# IO_board-ha-v3-rev1.net
KiCad netlist of a schematic drawn in EAGLE
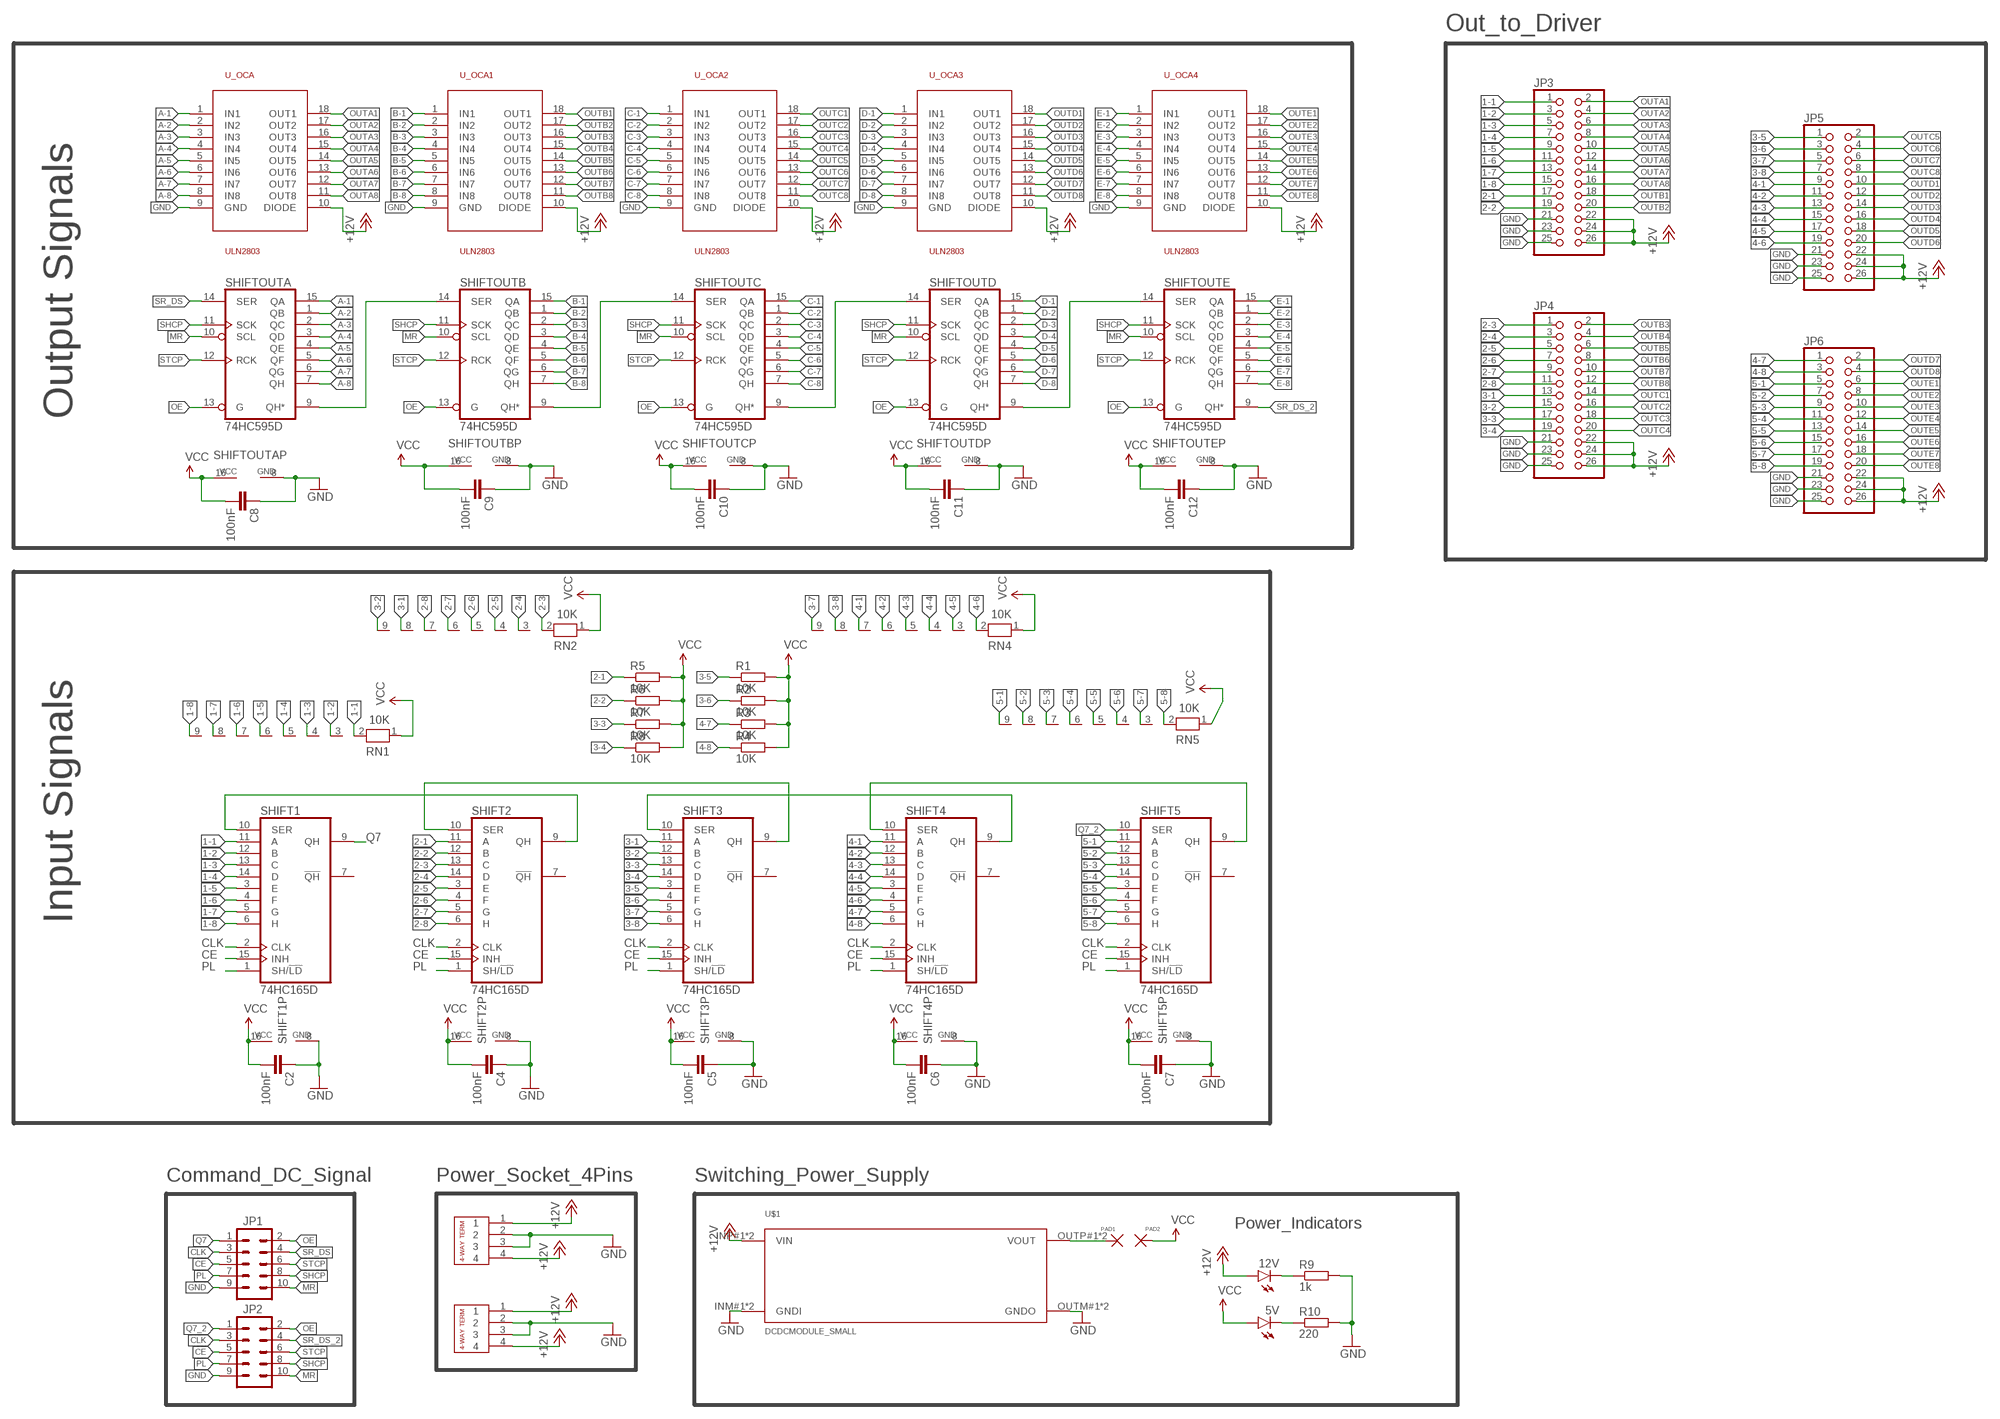
[diagram p0: schematic, sheet 1]

(export (version "E")
  (design (tool "Eeschema 10.0.6"))
  (components
    (comp (ref "5V")
      (value "LED3MM")
      (footprint "eagle-import:LED3MM")
      (libsource (lib "eagle-import") (part "LED3MM"))
    )
    (comp (ref "12V")
      (value "LED3MM")
      (footprint "eagle-import:LED3MM")
      (libsource (lib "eagle-import") (part "LED3MM"))
    )
    (comp (ref "C2")
      (value "100nF")
      (footprint "eagle-import:C0603K")
      (libsource (lib "eagle-import") (part "C-EUC0603K"))
    )
    (comp (ref "C4")
      (value "100nF")
      (footprint "eagle-import:C0603K")
      (libsource (lib "eagle-import") (part "C-EUC0603K"))
    )
    (comp (ref "C5")
      (value "100nF")
      (footprint "eagle-import:C0603K")
      (libsource (lib "eagle-import") (part "C-EUC0603K"))
    )
    (comp (ref "C6")
      (value "100nF")
      (footprint "eagle-import:C0603K")
      (libsource (lib "eagle-import") (part "C-EUC0603K"))
    )
    (comp (ref "C7")
      (value "100nF")
      (footprint "eagle-import:C0603K")
      (libsource (lib "eagle-import") (part "C-EUC0603K"))
    )
    (comp (ref "C8")
      (value "100nF")
      (footprint "eagle-import:C0603K")
      (libsource (lib "eagle-import") (part "C-EUC0603K"))
    )
    (comp (ref "C9")
      (value "100nF")
      (footprint "eagle-import:C0603K")
      (libsource (lib "eagle-import") (part "C-EUC0603K"))
    )
    (comp (ref "C10")
      (value "100nF")
      (footprint "eagle-import:C0603K")
      (libsource (lib "eagle-import") (part "C-EUC0603K"))
    )
    (comp (ref "C11")
      (value "100nF")
      (footprint "eagle-import:C0603K")
      (libsource (lib "eagle-import") (part "C-EUC0603K"))
    )
    (comp (ref "C12")
      (value "100nF")
      (footprint "eagle-import:C0603K")
      (libsource (lib "eagle-import") (part "C-EUC0603K"))
    )
    (comp (ref "J1")
      (value "4-PIN-CON-1759017")
      (footprint "eagle-import:4-PIN-CON-1759017")
      (libsource (lib "eagle-import") (part "4-PIN-CON-1759017"))
    )
    (comp (ref "J2")
      (value "4-PIN-CON-1759017")
      (footprint "eagle-import:4-PIN-CON-1759017")
      (libsource (lib "eagle-import") (part "4-PIN-CON-1759017"))
    )
    (comp (ref "JP1")
      (value "M05X2SHD")
      (footprint "eagle-import:2X5-SHROUDED")
      (libsource (lib "eagle-import") (part "M05X2SHD"))
    )
    (comp (ref "JP2")
      (value "M05X2SHD")
      (footprint "eagle-import:2X5-SHROUDED")
      (libsource (lib "eagle-import") (part "M05X2SHD"))
    )
    (comp (ref "JP3")
      (value "PINHD-2X13")
      (footprint "eagle-import:2X13")
      (libsource (lib "eagle-import") (part "PINHD-2X13"))
    )
    (comp (ref "JP4")
      (value "PINHD-2X13")
      (footprint "eagle-import:2X13")
      (libsource (lib "eagle-import") (part "PINHD-2X13"))
    )
    (comp (ref "JP5")
      (value "PINHD-2X13")
      (footprint "eagle-import:2X13")
      (libsource (lib "eagle-import") (part "PINHD-2X13"))
    )
    (comp (ref "JP6")
      (value "PINHD-2X13")
      (footprint "eagle-import:2X13")
      (libsource (lib "eagle-import") (part "PINHD-2X13"))
    )
    (comp (ref "R1")
      (value "10K")
      (footprint "eagle-import:R0603")
      (libsource (lib "eagle-import") (part "resistor_R-EU_R0603"))
    )
    (comp (ref "R2")
      (value "10K")
      (footprint "eagle-import:R0603")
      (libsource (lib "eagle-import") (part "resistor_R-EU_R0603"))
    )
    (comp (ref "R3")
      (value "10K")
      (footprint "eagle-import:R0603")
      (libsource (lib "eagle-import") (part "resistor_R-EU_R0603"))
    )
    (comp (ref "R4")
      (value "10K")
      (footprint "eagle-import:R0603")
      (libsource (lib "eagle-import") (part "resistor_R-EU_R0603"))
    )
    (comp (ref "R5")
      (value "10K")
      (footprint "eagle-import:R0603")
      (libsource (lib "eagle-import") (part "resistor_R-EU_R0603"))
    )
    (comp (ref "R6")
      (value "10K")
      (footprint "eagle-import:R0603")
      (libsource (lib "eagle-import") (part "resistor_R-EU_R0603"))
    )
    (comp (ref "R7")
      (value "10K")
      (footprint "eagle-import:R0603")
      (libsource (lib "eagle-import") (part "resistor_R-EU_R0603"))
    )
    (comp (ref "R8")
      (value "10K")
      (footprint "eagle-import:R0603")
      (libsource (lib "eagle-import") (part "resistor_R-EU_R0603"))
    )
    (comp (ref "R9")
      (value "1k")
      (footprint "eagle-import:R0805")
      (libsource (lib "eagle-import") (part "R-EU_R0805"))
    )
    (comp (ref "R10")
      (value "220")
      (footprint "eagle-import:R0805")
      (libsource (lib "eagle-import") (part "R-EU_R0805"))
    )
    (comp (ref "RN1")
      (value "10K")
      (footprint "eagle-import:RN-9")
      (libsource (lib "eagle-import") (part "RN08"))
    )
    (comp (ref "RN2")
      (value "10K")
      (footprint "eagle-import:RN-9")
      (libsource (lib "eagle-import") (part "RN08"))
    )
    (comp (ref "RN4")
      (value "10K")
      (footprint "eagle-import:RN-9")
      (libsource (lib "eagle-import") (part "RN08"))
    )
    (comp (ref "RN5")
      (value "10K")
      (footprint "eagle-import:RN-9")
      (libsource (lib "eagle-import") (part "RN08"))
    )
    (comp (ref "SHIFT1")
      (value "74HC165D")
      (footprint "eagle-import:SO16")
      (libsource (lib "eagle-import") (part "74165DHC"))
    )
    (comp (ref "SHIFT2")
      (value "74HC165D")
      (footprint "eagle-import:SO16")
      (libsource (lib "eagle-import") (part "74165DHC"))
    )
    (comp (ref "SHIFT3")
      (value "74HC165D")
      (footprint "eagle-import:SO16")
      (libsource (lib "eagle-import") (part "74165DHC"))
    )
    (comp (ref "SHIFT4")
      (value "74HC165D")
      (footprint "eagle-import:SO16")
      (libsource (lib "eagle-import") (part "74165DHC"))
    )
    (comp (ref "SHIFT5")
      (value "74HC165D")
      (footprint "eagle-import:SO16")
      (libsource (lib "eagle-import") (part "74165DHC"))
    )
    (comp (ref "SHIFTOUTA")
      (value "74HC595D")
      (footprint "eagle-import:SO16")
      (libsource (lib "eagle-import") (part "74595DHC"))
    )
    (comp (ref "SHIFTOUTB")
      (value "74HC595D")
      (footprint "eagle-import:SO16")
      (libsource (lib "eagle-import") (part "74595DHC"))
    )
    (comp (ref "SHIFTOUTC")
      (value "74HC595D")
      (footprint "eagle-import:SO16")
      (libsource (lib "eagle-import") (part "74595DHC"))
    )
    (comp (ref "SHIFTOUTD")
      (value "74HC595D")
      (footprint "eagle-import:SO16")
      (libsource (lib "eagle-import") (part "74595DHC"))
    )
    (comp (ref "SHIFTOUTE")
      (value "74HC595D")
      (footprint "eagle-import:SO16")
      (libsource (lib "eagle-import") (part "74595DHC"))
    )
    (comp (ref "U$1")
      (value "DCDCMODULE_SMALL")
      (footprint "eagle-import:DCDCMODULE-SMALL")
      (libsource (lib "eagle-import") (part "DCDCMODULE_SMALL"))
    )
    (comp (ref "U$2")
      (value "DOUBLE_SMALL_PAD")
      (footprint "eagle-import:DOUBLE_SMALL_PAD")
      (libsource (lib "eagle-import") (part "DOUBLE_SMALL_PAD"))
    )
    (comp (ref "U_OCA")
      (value "ULN2803")
      (footprint "eagle-import:SO18L")
      (libsource (lib "eagle-import") (part "ULN2803"))
    )
    (comp (ref "U_OCA1")
      (value "ULN2803")
      (footprint "eagle-import:SO18L")
      (libsource (lib "eagle-import") (part "ULN2803"))
    )
    (comp (ref "U_OCA2")
      (value "ULN2803")
      (footprint "eagle-import:SO18L")
      (libsource (lib "eagle-import") (part "ULN2803"))
    )
    (comp (ref "U_OCA3")
      (value "ULN2803")
      (footprint "eagle-import:SO18L")
      (libsource (lib "eagle-import") (part "ULN2803"))
    )
    (comp (ref "U_OCA4")
      (value "ULN2803")
      (footprint "eagle-import:SO18L")
      (libsource (lib "eagle-import") (part "ULN2803"))
    )
  )
  (nets
    (net (code "1") (name "+12V") (class "Default")
      (node (ref "12V") (pin "A") (pinfunction "A_A") (pintype "passive"))
      (node (ref "J1") (pin "1") (pinfunction "1_1") (pintype "bidirectional"))
      (node (ref "J1") (pin "4") (pinfunction "4_4") (pintype "bidirectional"))
      (node (ref "J2") (pin "1") (pinfunction "1_1") (pintype "bidirectional"))
      (node (ref "J2") (pin "4") (pinfunction "4_4") (pintype "bidirectional"))
      (node (ref "JP3") (pin "22") (pinfunction "22_22") (pintype "passive"))
      (node (ref "JP3") (pin "24") (pinfunction "24_24") (pintype "passive"))
      (node (ref "JP3") (pin "26") (pinfunction "26_26") (pintype "passive"))
      (node (ref "JP4") (pin "22") (pinfunction "22_22") (pintype "passive"))
      (node (ref "JP4") (pin "24") (pinfunction "24_24") (pintype "passive"))
      (node (ref "JP4") (pin "26") (pinfunction "26_26") (pintype "passive"))
      (node (ref "JP5") (pin "22") (pinfunction "22_22") (pintype "passive"))
      (node (ref "JP5") (pin "24") (pinfunction "24_24") (pintype "passive"))
      (node (ref "JP5") (pin "26") (pinfunction "26_26") (pintype "passive"))
      (node (ref "JP6") (pin "22") (pinfunction "22_22") (pintype "passive"))
      (node (ref "JP6") (pin "24") (pinfunction "24_24") (pintype "passive"))
      (node (ref "JP6") (pin "26") (pinfunction "26_26") (pintype "passive"))
      (node (ref "U$1") (pin "INP#1") (pinfunction "VIN_INP#1") (pintype "bidirectional"))
      (node (ref "U$1") (pin "INP#2") (pinfunction "VIN_INP#2") (pintype "bidirectional"))
      (node (ref "U_OCA") (pin "10") (pinfunction "DIODE_10") (pintype "power_in"))
      (node (ref "U_OCA1") (pin "10") (pinfunction "DIODE_10") (pintype "power_in"))
      (node (ref "U_OCA2") (pin "10") (pinfunction "DIODE_10") (pintype "power_in"))
      (node (ref "U_OCA3") (pin "10") (pinfunction "DIODE_10") (pintype "power_in"))
      (node (ref "U_OCA4") (pin "10") (pinfunction "DIODE_10") (pintype "power_in"))
    )
    (net (code "2") (name "1-1") (class "Default")
      (node (ref "JP3") (pin "1") (pinfunction "1_1") (pintype "passive"))
      (node (ref "RN1") (pin "2") (pinfunction "2_2") (pintype "passive"))
      (node (ref "SHIFT1") (pin "11") (pinfunction "A_11") (pintype "input"))
    )
    (net (code "3") (name "1-2") (class "Default")
      (node (ref "JP3") (pin "3") (pinfunction "3_3") (pintype "passive"))
      (node (ref "RN1") (pin "3") (pinfunction "3_3") (pintype "passive"))
      (node (ref "SHIFT1") (pin "12") (pinfunction "B_12") (pintype "input"))
    )
    (net (code "4") (name "1-3") (class "Default")
      (node (ref "JP3") (pin "5") (pinfunction "5_5") (pintype "passive"))
      (node (ref "RN1") (pin "4") (pinfunction "4_4") (pintype "passive"))
      (node (ref "SHIFT1") (pin "13") (pinfunction "C_13") (pintype "input"))
    )
    (net (code "5") (name "1-4") (class "Default")
      (node (ref "JP3") (pin "7") (pinfunction "7_7") (pintype "passive"))
      (node (ref "RN1") (pin "5") (pinfunction "5_5") (pintype "passive"))
      (node (ref "SHIFT1") (pin "14") (pinfunction "D_14") (pintype "input"))
    )
    (net (code "6") (name "1-5") (class "Default")
      (node (ref "JP3") (pin "9") (pinfunction "9_9") (pintype "passive"))
      (node (ref "RN1") (pin "6") (pinfunction "6_6") (pintype "passive"))
      (node (ref "SHIFT1") (pin "3") (pinfunction "E_3") (pintype "input"))
    )
    (net (code "7") (name "1-6") (class "Default")
      (node (ref "JP3") (pin "11") (pinfunction "11_11") (pintype "passive"))
      (node (ref "RN1") (pin "7") (pinfunction "7_7") (pintype "passive"))
      (node (ref "SHIFT1") (pin "4") (pinfunction "F_4") (pintype "input"))
    )
    (net (code "8") (name "1-7") (class "Default")
      (node (ref "JP3") (pin "13") (pinfunction "13_13") (pintype "passive"))
      (node (ref "RN1") (pin "8") (pinfunction "8_8") (pintype "passive"))
      (node (ref "SHIFT1") (pin "5") (pinfunction "G_5") (pintype "input"))
    )
    (net (code "9") (name "1-8") (class "Default")
      (node (ref "JP3") (pin "15") (pinfunction "15_15") (pintype "passive"))
      (node (ref "RN1") (pin "9") (pinfunction "9_9") (pintype "passive"))
      (node (ref "SHIFT1") (pin "6") (pinfunction "H_6") (pintype "input"))
    )
    (net (code "10") (name "2-1") (class "Default")
      (node (ref "JP3") (pin "17") (pinfunction "17_17") (pintype "passive"))
      (node (ref "R5") (pin "1") (pinfunction "1_1") (pintype "passive"))
      (node (ref "SHIFT2") (pin "11") (pinfunction "A_11") (pintype "input"))
    )
    (net (code "11") (name "2-2") (class "Default")
      (node (ref "JP3") (pin "19") (pinfunction "19_19") (pintype "passive"))
      (node (ref "R6") (pin "1") (pinfunction "1_1") (pintype "passive"))
      (node (ref "SHIFT2") (pin "12") (pinfunction "B_12") (pintype "input"))
    )
    (net (code "12") (name "2-3") (class "Default")
      (node (ref "JP4") (pin "1") (pinfunction "1_1") (pintype "passive"))
      (node (ref "RN2") (pin "2") (pinfunction "2_2") (pintype "passive"))
      (node (ref "SHIFT2") (pin "13") (pinfunction "C_13") (pintype "input"))
    )
    (net (code "13") (name "2-4") (class "Default")
      (node (ref "JP4") (pin "3") (pinfunction "3_3") (pintype "passive"))
      (node (ref "RN2") (pin "3") (pinfunction "3_3") (pintype "passive"))
      (node (ref "SHIFT2") (pin "14") (pinfunction "D_14") (pintype "input"))
    )
    (net (code "14") (name "2-5") (class "Default")
      (node (ref "JP4") (pin "5") (pinfunction "5_5") (pintype "passive"))
      (node (ref "RN2") (pin "4") (pinfunction "4_4") (pintype "passive"))
      (node (ref "SHIFT2") (pin "3") (pinfunction "E_3") (pintype "input"))
    )
    (net (code "15") (name "2-6") (class "Default")
      (node (ref "JP4") (pin "7") (pinfunction "7_7") (pintype "passive"))
      (node (ref "RN2") (pin "5") (pinfunction "5_5") (pintype "passive"))
      (node (ref "SHIFT2") (pin "4") (pinfunction "F_4") (pintype "input"))
    )
    (net (code "16") (name "2-7") (class "Default")
      (node (ref "JP4") (pin "9") (pinfunction "9_9") (pintype "passive"))
      (node (ref "RN2") (pin "6") (pinfunction "6_6") (pintype "passive"))
      (node (ref "SHIFT2") (pin "5") (pinfunction "G_5") (pintype "input"))
    )
    (net (code "17") (name "2-8") (class "Default")
      (node (ref "JP4") (pin "11") (pinfunction "11_11") (pintype "passive"))
      (node (ref "RN2") (pin "7") (pinfunction "7_7") (pintype "passive"))
      (node (ref "SHIFT2") (pin "6") (pinfunction "H_6") (pintype "input"))
    )
    (net (code "18") (name "3-1") (class "Default")
      (node (ref "JP4") (pin "13") (pinfunction "13_13") (pintype "passive"))
      (node (ref "RN2") (pin "8") (pinfunction "8_8") (pintype "passive"))
      (node (ref "SHIFT3") (pin "11") (pinfunction "A_11") (pintype "input"))
    )
    (net (code "19") (name "3-2") (class "Default")
      (node (ref "JP4") (pin "15") (pinfunction "15_15") (pintype "passive"))
      (node (ref "RN2") (pin "9") (pinfunction "9_9") (pintype "passive"))
      (node (ref "SHIFT3") (pin "12") (pinfunction "B_12") (pintype "input"))
    )
    (net (code "20") (name "3-3") (class "Default")
      (node (ref "JP4") (pin "17") (pinfunction "17_17") (pintype "passive"))
      (node (ref "R7") (pin "1") (pinfunction "1_1") (pintype "passive"))
      (node (ref "SHIFT3") (pin "13") (pinfunction "C_13") (pintype "input"))
    )
    (net (code "21") (name "3-4") (class "Default")
      (node (ref "JP4") (pin "19") (pinfunction "19_19") (pintype "passive"))
      (node (ref "R8") (pin "1") (pinfunction "1_1") (pintype "passive"))
      (node (ref "SHIFT3") (pin "14") (pinfunction "D_14") (pintype "input"))
    )
    (net (code "22") (name "3-5") (class "Default")
      (node (ref "JP5") (pin "1") (pinfunction "1_1") (pintype "passive"))
      (node (ref "R1") (pin "1") (pinfunction "1_1") (pintype "passive"))
      (node (ref "SHIFT3") (pin "3") (pinfunction "E_3") (pintype "input"))
    )
    (net (code "23") (name "3-6") (class "Default")
      (node (ref "JP5") (pin "3") (pinfunction "3_3") (pintype "passive"))
      (node (ref "R2") (pin "1") (pinfunction "1_1") (pintype "passive"))
      (node (ref "SHIFT3") (pin "4") (pinfunction "F_4") (pintype "input"))
    )
    (net (code "24") (name "3-7") (class "Default")
      (node (ref "JP5") (pin "5") (pinfunction "5_5") (pintype "passive"))
      (node (ref "RN4") (pin "9") (pinfunction "9_9") (pintype "passive"))
      (node (ref "SHIFT3") (pin "5") (pinfunction "G_5") (pintype "input"))
    )
    (net (code "25") (name "3-8") (class "Default")
      (node (ref "JP5") (pin "7") (pinfunction "7_7") (pintype "passive"))
      (node (ref "RN4") (pin "8") (pinfunction "8_8") (pintype "passive"))
      (node (ref "SHIFT3") (pin "6") (pinfunction "H_6") (pintype "input"))
    )
    (net (code "26") (name "4-1") (class "Default")
      (node (ref "JP5") (pin "9") (pinfunction "9_9") (pintype "passive"))
      (node (ref "RN4") (pin "7") (pinfunction "7_7") (pintype "passive"))
      (node (ref "SHIFT4") (pin "11") (pinfunction "A_11") (pintype "input"))
    )
    (net (code "27") (name "4-2") (class "Default")
      (node (ref "JP5") (pin "11") (pinfunction "11_11") (pintype "passive"))
      (node (ref "RN4") (pin "6") (pinfunction "6_6") (pintype "passive"))
      (node (ref "SHIFT4") (pin "12") (pinfunction "B_12") (pintype "input"))
    )
    (net (code "28") (name "4-3") (class "Default")
      (node (ref "JP5") (pin "13") (pinfunction "13_13") (pintype "passive"))
      (node (ref "RN4") (pin "5") (pinfunction "5_5") (pintype "passive"))
      (node (ref "SHIFT4") (pin "13") (pinfunction "C_13") (pintype "input"))
    )
    (net (code "29") (name "4-4") (class "Default")
      (node (ref "JP5") (pin "15") (pinfunction "15_15") (pintype "passive"))
      (node (ref "RN4") (pin "4") (pinfunction "4_4") (pintype "passive"))
      (node (ref "SHIFT4") (pin "14") (pinfunction "D_14") (pintype "input"))
    )
    (net (code "30") (name "4-5") (class "Default")
      (node (ref "JP5") (pin "17") (pinfunction "17_17") (pintype "passive"))
      (node (ref "RN4") (pin "3") (pinfunction "3_3") (pintype "passive"))
      (node (ref "SHIFT4") (pin "3") (pinfunction "E_3") (pintype "input"))
    )
    (net (code "31") (name "4-6") (class "Default")
      (node (ref "JP5") (pin "19") (pinfunction "19_19") (pintype "passive"))
      (node (ref "RN4") (pin "2") (pinfunction "2_2") (pintype "passive"))
      (node (ref "SHIFT4") (pin "4") (pinfunction "F_4") (pintype "input"))
    )
    (net (code "32") (name "4-7") (class "Default")
      (node (ref "JP6") (pin "1") (pinfunction "1_1") (pintype "passive"))
      (node (ref "R3") (pin "1") (pinfunction "1_1") (pintype "passive"))
      (node (ref "SHIFT4") (pin "5") (pinfunction "G_5") (pintype "input"))
    )
    (net (code "33") (name "4-8") (class "Default")
      (node (ref "JP6") (pin "3") (pinfunction "3_3") (pintype "passive"))
      (node (ref "R4") (pin "1") (pinfunction "1_1") (pintype "passive"))
      (node (ref "SHIFT4") (pin "6") (pinfunction "H_6") (pintype "input"))
    )
    (net (code "34") (name "5-1") (class "Default")
      (node (ref "JP6") (pin "5") (pinfunction "5_5") (pintype "passive"))
      (node (ref "RN5") (pin "9") (pinfunction "9_9") (pintype "passive"))
      (node (ref "SHIFT5") (pin "11") (pinfunction "A_11") (pintype "input"))
    )
    (net (code "35") (name "5-2") (class "Default")
      (node (ref "JP6") (pin "7") (pinfunction "7_7") (pintype "passive"))
      (node (ref "RN5") (pin "8") (pinfunction "8_8") (pintype "passive"))
      (node (ref "SHIFT5") (pin "12") (pinfunction "B_12") (pintype "input"))
    )
    (net (code "36") (name "5-3") (class "Default")
      (node (ref "JP6") (pin "9") (pinfunction "9_9") (pintype "passive"))
      (node (ref "RN5") (pin "7") (pinfunction "7_7") (pintype "passive"))
      (node (ref "SHIFT5") (pin "13") (pinfunction "C_13") (pintype "input"))
    )
    (net (code "37") (name "5-4") (class "Default")
      (node (ref "JP6") (pin "11") (pinfunction "11_11") (pintype "passive"))
      (node (ref "RN5") (pin "6") (pinfunction "6_6") (pintype "passive"))
      (node (ref "SHIFT5") (pin "14") (pinfunction "D_14") (pintype "input"))
    )
    (net (code "38") (name "5-5") (class "Default")
      (node (ref "JP6") (pin "13") (pinfunction "13_13") (pintype "passive"))
      (node (ref "RN5") (pin "5") (pinfunction "5_5") (pintype "passive"))
      (node (ref "SHIFT5") (pin "3") (pinfunction "E_3") (pintype "input"))
    )
    (net (code "39") (name "5-6") (class "Default")
      (node (ref "JP6") (pin "15") (pinfunction "15_15") (pintype "passive"))
      (node (ref "RN5") (pin "4") (pinfunction "4_4") (pintype "passive"))
      (node (ref "SHIFT5") (pin "4") (pinfunction "F_4") (pintype "input"))
    )
    (net (code "40") (name "5-7") (class "Default")
      (node (ref "JP6") (pin "17") (pinfunction "17_17") (pintype "passive"))
      (node (ref "RN5") (pin "3") (pinfunction "3_3") (pintype "passive"))
      (node (ref "SHIFT5") (pin "5") (pinfunction "G_5") (pintype "input"))
    )
    (net (code "41") (name "5-8") (class "Default")
      (node (ref "JP6") (pin "19") (pinfunction "19_19") (pintype "passive"))
      (node (ref "RN5") (pin "2") (pinfunction "2_2") (pintype "passive"))
      (node (ref "SHIFT5") (pin "6") (pinfunction "H_6") (pintype "input"))
    )
    (net (code "42") (name "A-1") (class "Default")
      (node (ref "SHIFTOUTA") (pin "15") (pinfunction "QA_15") (pintype "tri_state"))
      (node (ref "U_OCA") (pin "1") (pinfunction "IN1_1") (pintype "input"))
    )
    (net (code "43") (name "A-2") (class "Default")
      (node (ref "SHIFTOUTA") (pin "1") (pinfunction "QB_1") (pintype "tri_state"))
      (node (ref "U_OCA") (pin "2") (pinfunction "IN2_2") (pintype "input"))
    )
    (net (code "44") (name "A-3") (class "Default")
      (node (ref "SHIFTOUTA") (pin "2") (pinfunction "QC_2") (pintype "tri_state"))
      (node (ref "U_OCA") (pin "3") (pinfunction "IN3_3") (pintype "input"))
    )
    (net (code "45") (name "A-4") (class "Default")
      (node (ref "SHIFTOUTA") (pin "3") (pinfunction "QD_3") (pintype "tri_state"))
      (node (ref "U_OCA") (pin "4") (pinfunction "IN4_4") (pintype "input"))
    )
    (net (code "46") (name "A-5") (class "Default")
      (node (ref "SHIFTOUTA") (pin "4") (pinfunction "QE_4") (pintype "tri_state"))
      (node (ref "U_OCA") (pin "5") (pinfunction "IN5_5") (pintype "input"))
    )
    (net (code "47") (name "A-6") (class "Default")
      (node (ref "SHIFTOUTA") (pin "5") (pinfunction "QF_5") (pintype "tri_state"))
      (node (ref "U_OCA") (pin "6") (pinfunction "IN6_6") (pintype "input"))
    )
    (net (code "48") (name "A-7") (class "Default")
      (node (ref "SHIFTOUTA") (pin "6") (pinfunction "QG_6") (pintype "tri_state"))
      (node (ref "U_OCA") (pin "7") (pinfunction "IN7_7") (pintype "input"))
    )
    (net (code "49") (name "A-8") (class "Default")
      (node (ref "SHIFTOUTA") (pin "7") (pinfunction "QH_7") (pintype "tri_state"))
      (node (ref "U_OCA") (pin "8") (pinfunction "IN8_8") (pintype "input"))
    )
    (net (code "50") (name "B-1") (class "Default")
      (node (ref "SHIFTOUTB") (pin "15") (pinfunction "QA_15") (pintype "tri_state"))
      (node (ref "U_OCA1") (pin "1") (pinfunction "IN1_1") (pintype "input"))
    )
    (net (code "51") (name "B-2") (class "Default")
      (node (ref "SHIFTOUTB") (pin "1") (pinfunction "QB_1") (pintype "tri_state"))
      (node (ref "U_OCA1") (pin "2") (pinfunction "IN2_2") (pintype "input"))
    )
    (net (code "52") (name "B-3") (class "Default")
      (node (ref "SHIFTOUTB") (pin "2") (pinfunction "QC_2") (pintype "tri_state"))
      (node (ref "U_OCA1") (pin "3") (pinfunction "IN3_3") (pintype "input"))
    )
    (net (code "53") (name "B-4") (class "Default")
      (node (ref "SHIFTOUTB") (pin "3") (pinfunction "QD_3") (pintype "tri_state"))
      (node (ref "U_OCA1") (pin "4") (pinfunction "IN4_4") (pintype "input"))
    )
    (net (code "54") (name "B-5") (class "Default")
      (node (ref "SHIFTOUTB") (pin "4") (pinfunction "QE_4") (pintype "tri_state"))
      (node (ref "U_OCA1") (pin "5") (pinfunction "IN5_5") (pintype "input"))
    )
    (net (code "55") (name "B-6") (class "Default")
      (node (ref "SHIFTOUTB") (pin "5") (pinfunction "QF_5") (pintype "tri_state"))
      (node (ref "U_OCA1") (pin "6") (pinfunction "IN6_6") (pintype "input"))
    )
    (net (code "56") (name "B-7") (class "Default")
      (node (ref "SHIFTOUTB") (pin "6") (pinfunction "QG_6") (pintype "tri_state"))
      (node (ref "U_OCA1") (pin "7") (pinfunction "IN7_7") (pintype "input"))
    )
    (net (code "57") (name "B-8") (class "Default")
      (node (ref "SHIFTOUTB") (pin "7") (pinfunction "QH_7") (pintype "tri_state"))
      (node (ref "U_OCA1") (pin "8") (pinfunction "IN8_8") (pintype "input"))
    )
    (net (code "58") (name "C-1") (class "Default")
      (node (ref "SHIFTOUTC") (pin "15") (pinfunction "QA_15") (pintype "tri_state"))
      (node (ref "U_OCA2") (pin "1") (pinfunction "IN1_1") (pintype "input"))
    )
    (net (code "59") (name "C-2") (class "Default")
      (node (ref "SHIFTOUTC") (pin "1") (pinfunction "QB_1") (pintype "tri_state"))
      (node (ref "U_OCA2") (pin "2") (pinfunction "IN2_2") (pintype "input"))
    )
    (net (code "60") (name "C-3") (class "Default")
      (node (ref "SHIFTOUTC") (pin "2") (pinfunction "QC_2") (pintype "tri_state"))
      (node (ref "U_OCA2") (pin "3") (pinfunction "IN3_3") (pintype "input"))
    )
    (net (code "61") (name "C-4") (class "Default")
      (node (ref "SHIFTOUTC") (pin "3") (pinfunction "QD_3") (pintype "tri_state"))
      (node (ref "U_OCA2") (pin "4") (pinfunction "IN4_4") (pintype "input"))
    )
    (net (code "62") (name "C-5") (class "Default")
      (node (ref "SHIFTOUTC") (pin "4") (pinfunction "QE_4") (pintype "tri_state"))
      (node (ref "U_OCA2") (pin "5") (pinfunction "IN5_5") (pintype "input"))
    )
    (net (code "63") (name "C-6") (class "Default")
      (node (ref "SHIFTOUTC") (pin "5") (pinfunction "QF_5") (pintype "tri_state"))
      (node (ref "U_OCA2") (pin "6") (pinfunction "IN6_6") (pintype "input"))
    )
    (net (code "64") (name "C-7") (class "Default")
      (node (ref "SHIFTOUTC") (pin "6") (pinfunction "QG_6") (pintype "tri_state"))
      (node (ref "U_OCA2") (pin "7") (pinfunction "IN7_7") (pintype "input"))
    )
    (net (code "65") (name "C-8") (class "Default")
      (node (ref "SHIFTOUTC") (pin "7") (pinfunction "QH_7") (pintype "tri_state"))
      (node (ref "U_OCA2") (pin "8") (pinfunction "IN8_8") (pintype "input"))
    )
    (net (code "66") (name "CE") (class "Default")
      (node (ref "JP1") (pin "5") (pinfunction "5_5") (pintype "passive"))
      (node (ref "JP2") (pin "5") (pinfunction "5_5") (pintype "passive"))
      (node (ref "SHIFT1") (pin "15") (pinfunction "INH_15") (pintype "input"))
      (node (ref "SHIFT2") (pin "15") (pinfunction "INH_15") (pintype "input"))
      (node (ref "SHIFT3") (pin "15") (pinfunction "INH_15") (pintype "input"))
      (node (ref "SHIFT4") (pin "15") (pinfunction "INH_15") (pintype "input"))
      (node (ref "SHIFT5") (pin "15") (pinfunction "INH_15") (pintype "input"))
    )
    (net (code "67") (name "CLK") (class "Default")
      (node (ref "JP1") (pin "3") (pinfunction "3_3") (pintype "passive"))
      (node (ref "JP2") (pin "3") (pinfunction "3_3") (pintype "passive"))
      (node (ref "SHIFT1") (pin "2") (pinfunction "CLK_2") (pintype "input"))
      (node (ref "SHIFT2") (pin "2") (pinfunction "CLK_2") (pintype "input"))
      (node (ref "SHIFT3") (pin "2") (pinfunction "CLK_2") (pintype "input"))
      (node (ref "SHIFT4") (pin "2") (pinfunction "CLK_2") (pintype "input"))
      (node (ref "SHIFT5") (pin "2") (pinfunction "CLK_2") (pintype "input"))
    )
    (net (code "68") (name "D-1") (class "Default")
      (node (ref "SHIFTOUTD") (pin "15") (pinfunction "QA_15") (pintype "tri_state"))
      (node (ref "U_OCA3") (pin "1") (pinfunction "IN1_1") (pintype "input"))
    )
    (net (code "69") (name "D-2") (class "Default")
      (node (ref "SHIFTOUTD") (pin "1") (pinfunction "QB_1") (pintype "tri_state"))
      (node (ref "U_OCA3") (pin "2") (pinfunction "IN2_2") (pintype "input"))
    )
    (net (code "70") (name "D-3") (class "Default")
      (node (ref "SHIFTOUTD") (pin "2") (pinfunction "QC_2") (pintype "tri_state"))
      (node (ref "U_OCA3") (pin "3") (pinfunction "IN3_3") (pintype "input"))
    )
    (net (code "71") (name "D-4") (class "Default")
      (node (ref "SHIFTOUTD") (pin "3") (pinfunction "QD_3") (pintype "tri_state"))
      (node (ref "U_OCA3") (pin "4") (pinfunction "IN4_4") (pintype "input"))
    )
    (net (code "72") (name "D-5") (class "Default")
      (node (ref "SHIFTOUTD") (pin "4") (pinfunction "QE_4") (pintype "tri_state"))
      (node (ref "U_OCA3") (pin "5") (pinfunction "IN5_5") (pintype "input"))
    )
    (net (code "73") (name "D-6") (class "Default")
      (node (ref "SHIFTOUTD") (pin "5") (pinfunction "QF_5") (pintype "tri_state"))
      (node (ref "U_OCA3") (pin "6") (pinfunction "IN6_6") (pintype "input"))
    )
    (net (code "74") (name "D-7") (class "Default")
      (node (ref "SHIFTOUTD") (pin "6") (pinfunction "QG_6") (pintype "tri_state"))
      (node (ref "U_OCA3") (pin "7") (pinfunction "IN7_7") (pintype "input"))
    )
    (net (code "75") (name "D-8") (class "Default")
      (node (ref "SHIFTOUTD") (pin "7") (pinfunction "QH_7") (pintype "tri_state"))
      (node (ref "U_OCA3") (pin "8") (pinfunction "IN8_8") (pintype "input"))
    )
    (net (code "76") (name "E-1") (class "Default")
      (node (ref "SHIFTOUTE") (pin "15") (pinfunction "QA_15") (pintype "tri_state"))
      (node (ref "U_OCA4") (pin "1") (pinfunction "IN1_1") (pintype "input"))
    )
    (net (code "77") (name "E-2") (class "Default")
      (node (ref "SHIFTOUTE") (pin "1") (pinfunction "QB_1") (pintype "tri_state"))
      (node (ref "U_OCA4") (pin "2") (pinfunction "IN2_2") (pintype "input"))
    )
    (net (code "78") (name "E-3") (class "Default")
      (node (ref "SHIFTOUTE") (pin "2") (pinfunction "QC_2") (pintype "tri_state"))
      (node (ref "U_OCA4") (pin "3") (pinfunction "IN3_3") (pintype "input"))
    )
    (net (code "79") (name "E-4") (class "Default")
      (node (ref "SHIFTOUTE") (pin "3") (pinfunction "QD_3") (pintype "tri_state"))
      (node (ref "U_OCA4") (pin "4") (pinfunction "IN4_4") (pintype "input"))
    )
    (net (code "80") (name "E-5") (class "Default")
      (node (ref "SHIFTOUTE") (pin "4") (pinfunction "QE_4") (pintype "tri_state"))
      (node (ref "U_OCA4") (pin "5") (pinfunction "IN5_5") (pintype "input"))
    )
    (net (code "81") (name "E-6") (class "Default")
      (node (ref "SHIFTOUTE") (pin "5") (pinfunction "QF_5") (pintype "tri_state"))
      (node (ref "U_OCA4") (pin "6") (pinfunction "IN6_6") (pintype "input"))
    )
    (net (code "82") (name "E-7") (class "Default")
      (node (ref "SHIFTOUTE") (pin "6") (pinfunction "QG_6") (pintype "tri_state"))
      (node (ref "U_OCA4") (pin "7") (pinfunction "IN7_7") (pintype "input"))
    )
    (net (code "83") (name "E-8") (class "Default")
      (node (ref "SHIFTOUTE") (pin "7") (pinfunction "QH_7") (pintype "tri_state"))
      (node (ref "U_OCA4") (pin "8") (pinfunction "IN8_8") (pintype "input"))
    )
    (net (code "84") (name "GND") (class "Default")
      (node (ref "C10") (pin "1") (pinfunction "1_1") (pintype "passive"))
      (node (ref "C11") (pin "1") (pinfunction "1_1") (pintype "passive"))
      (node (ref "C12") (pin "1") (pinfunction "1_1") (pintype "passive"))
      (node (ref "C2") (pin "1") (pinfunction "1_1") (pintype "passive"))
      (node (ref "C4") (pin "1") (pinfunction "1_1") (pintype "passive"))
      (node (ref "C5") (pin "1") (pinfunction "1_1") (pintype "passive"))
      (node (ref "C6") (pin "1") (pinfunction "1_1") (pintype "passive"))
      (node (ref "C7") (pin "1") (pinfunction "1_1") (pintype "passive"))
      (node (ref "C8") (pin "1") (pinfunction "1_1") (pintype "passive"))
      (node (ref "C9") (pin "1") (pinfunction "1_1") (pintype "passive"))
      (node (ref "J1") (pin "2") (pinfunction "2_2") (pintype "bidirectional"))
      (node (ref "J1") (pin "3") (pinfunction "3_3") (pintype "bidirectional"))
      (node (ref "J2") (pin "2") (pinfunction "2_2") (pintype "bidirectional"))
      (node (ref "J2") (pin "3") (pinfunction "3_3") (pintype "bidirectional"))
      (node (ref "JP1") (pin "9") (pinfunction "9_9") (pintype "passive"))
      (node (ref "JP2") (pin "9") (pinfunction "9_9") (pintype "passive"))
      (node (ref "JP3") (pin "21") (pinfunction "21_21") (pintype "passive"))
      (node (ref "JP3") (pin "23") (pinfunction "23_23") (pintype "passive"))
      (node (ref "JP3") (pin "25") (pinfunction "25_25") (pintype "passive"))
      (node (ref "JP4") (pin "21") (pinfunction "21_21") (pintype "passive"))
      (node (ref "JP4") (pin "23") (pinfunction "23_23") (pintype "passive"))
      (node (ref "JP4") (pin "25") (pinfunction "25_25") (pintype "passive"))
      (node (ref "JP5") (pin "21") (pinfunction "21_21") (pintype "passive"))
      (node (ref "JP5") (pin "23") (pinfunction "23_23") (pintype "passive"))
      (node (ref "JP5") (pin "25") (pinfunction "25_25") (pintype "passive"))
      (node (ref "JP6") (pin "21") (pinfunction "21_21") (pintype "passive"))
      (node (ref "JP6") (pin "23") (pinfunction "23_23") (pintype "passive"))
      (node (ref "JP6") (pin "25") (pinfunction "25_25") (pintype "passive"))
      (node (ref "R10") (pin "2") (pinfunction "2_2") (pintype "passive"))
      (node (ref "R9") (pin "2") (pinfunction "2_2") (pintype "passive"))
      (node (ref "SHIFT1") (pin "8") (pinfunction "GND_8") (pintype "power_in"))
      (node (ref "SHIFT2") (pin "8") (pinfunction "GND_8") (pintype "power_in"))
      (node (ref "SHIFT3") (pin "8") (pinfunction "GND_8") (pintype "power_in"))
      (node (ref "SHIFT4") (pin "8") (pinfunction "GND_8") (pintype "power_in"))
      (node (ref "SHIFT5") (pin "8") (pinfunction "GND_8") (pintype "power_in"))
      (node (ref "SHIFTOUTA") (pin "8") (pinfunction "GND_8") (pintype "power_in"))
      (node (ref "SHIFTOUTB") (pin "8") (pinfunction "GND_8") (pintype "power_in"))
      (node (ref "SHIFTOUTC") (pin "8") (pinfunction "GND_8") (pintype "power_in"))
      (node (ref "SHIFTOUTD") (pin "8") (pinfunction "GND_8") (pintype "power_in"))
      (node (ref "SHIFTOUTE") (pin "8") (pinfunction "GND_8") (pintype "power_in"))
      (node (ref "U$1") (pin "INM#1") (pinfunction "GNDI_INM#1") (pintype "bidirectional"))
      (node (ref "U$1") (pin "INM#2") (pinfunction "GNDI_INM#2") (pintype "bidirectional"))
      (node (ref "U$1") (pin "OUTM#1") (pinfunction "GNDO_OUTM#1") (pintype "bidirectional"))
      (node (ref "U$1") (pin "OUTM#2") (pinfunction "GNDO_OUTM#2") (pintype "bidirectional"))
      (node (ref "U_OCA") (pin "9") (pinfunction "GND_9") (pintype "power_in"))
      (node (ref "U_OCA1") (pin "9") (pinfunction "GND_9") (pintype "power_in"))
      (node (ref "U_OCA2") (pin "9") (pinfunction "GND_9") (pintype "power_in"))
      (node (ref "U_OCA3") (pin "9") (pinfunction "GND_9") (pintype "power_in"))
      (node (ref "U_OCA4") (pin "9") (pinfunction "GND_9") (pintype "power_in"))
    )
    (net (code "85") (name "MR") (class "Default")
      (node (ref "JP1") (pin "10") (pinfunction "10_10") (pintype "passive"))
      (node (ref "JP2") (pin "10") (pinfunction "10_10") (pintype "passive"))
      (node (ref "SHIFTOUTA") (pin "10") (pinfunction "SCL_10") (pintype "input"))
      (node (ref "SHIFTOUTB") (pin "10") (pinfunction "SCL_10") (pintype "input"))
      (node (ref "SHIFTOUTC") (pin "10") (pinfunction "SCL_10") (pintype "input"))
      (node (ref "SHIFTOUTD") (pin "10") (pinfunction "SCL_10") (pintype "input"))
      (node (ref "SHIFTOUTE") (pin "10") (pinfunction "SCL_10") (pintype "input"))
    )
    (net (code "86") (name "Net-(5V-C)") (class "Default")
      (node (ref "5V") (pin "K") (pinfunction "C_K") (pintype "passive"))
      (node (ref "R10") (pin "1") (pinfunction "1_1") (pintype "passive"))
    )
    (net (code "87") (name "Net-(12V-C)") (class "Default")
      (node (ref "12V") (pin "K") (pinfunction "C_K") (pintype "passive"))
      (node (ref "R9") (pin "1") (pinfunction "1_1") (pintype "passive"))
    )
    (net (code "88") (name "Net-(SHIFT1A-SER)") (class "Default")
      (node (ref "SHIFT1") (pin "10") (pinfunction "SER_10") (pintype "input"))
      (node (ref "SHIFT2") (pin "9") (pinfunction "QH_9") (pintype "output"))
    )
    (net (code "89") (name "Net-(SHIFT2A-SER)") (class "Default")
      (node (ref "SHIFT2") (pin "10") (pinfunction "SER_10") (pintype "input"))
      (node (ref "SHIFT3") (pin "9") (pinfunction "QH_9") (pintype "output"))
    )
    (net (code "90") (name "Net-(SHIFT3A-SER)") (class "Default")
      (node (ref "SHIFT3") (pin "10") (pinfunction "SER_10") (pintype "input"))
      (node (ref "SHIFT4") (pin "9") (pinfunction "QH_9") (pintype "output"))
    )
    (net (code "91") (name "Net-(SHIFT4A-SER)") (class "Default")
      (node (ref "SHIFT4") (pin "10") (pinfunction "SER_10") (pintype "input"))
      (node (ref "SHIFT5") (pin "9") (pinfunction "QH_9") (pintype "output"))
    )
    (net (code "92") (name "Net-(SHIFTOUTAA-QH*)") (class "Default")
      (node (ref "SHIFTOUTA") (pin "9") (pinfunction "QH*_9") (pintype "tri_state"))
      (node (ref "SHIFTOUTB") (pin "14") (pinfunction "SER_14") (pintype "input"))
    )
    (net (code "93") (name "Net-(SHIFTOUTBA-QH*)") (class "Default")
      (node (ref "SHIFTOUTB") (pin "9") (pinfunction "QH*_9") (pintype "tri_state"))
      (node (ref "SHIFTOUTC") (pin "14") (pinfunction "SER_14") (pintype "input"))
    )
    (net (code "94") (name "Net-(SHIFTOUTCA-QH*)") (class "Default")
      (node (ref "SHIFTOUTC") (pin "9") (pinfunction "QH*_9") (pintype "tri_state"))
      (node (ref "SHIFTOUTD") (pin "14") (pinfunction "SER_14") (pintype "input"))
    )
    (net (code "95") (name "Net-(SHIFTOUTDA-QH*)") (class "Default")
      (node (ref "SHIFTOUTD") (pin "9") (pinfunction "QH*_9") (pintype "tri_state"))
      (node (ref "SHIFTOUTE") (pin "14") (pinfunction "SER_14") (pintype "input"))
    )
    (net (code "96") (name "Net-(U$1-VOUT-PadOUTP#1)") (class "Default")
      (node (ref "U$1") (pin "OUTP#1") (pinfunction "VOUT_OUTP#1") (pintype "bidirectional"))
      (node (ref "U$1") (pin "OUTP#2") (pinfunction "VOUT_OUTP#2") (pintype "bidirectional"))
      (node (ref "U$2") (pin "PAD1") (pinfunction "PAD1_PAD1") (pintype "bidirectional"))
    )
    (net (code "97") (name "OE") (class "Default")
      (node (ref "JP1") (pin "2") (pinfunction "2_2") (pintype "passive"))
      (node (ref "JP2") (pin "2") (pinfunction "2_2") (pintype "passive"))
      (node (ref "SHIFTOUTA") (pin "13") (pinfunction "G_13") (pintype "input"))
      (node (ref "SHIFTOUTB") (pin "13") (pinfunction "G_13") (pintype "input"))
      (node (ref "SHIFTOUTC") (pin "13") (pinfunction "G_13") (pintype "input"))
      (node (ref "SHIFTOUTD") (pin "13") (pinfunction "G_13") (pintype "input"))
      (node (ref "SHIFTOUTE") (pin "13") (pinfunction "G_13") (pintype "input"))
    )
    (net (code "98") (name "OUTA1") (class "Default")
      (node (ref "JP3") (pin "2") (pinfunction "2_2") (pintype "passive"))
      (node (ref "U_OCA") (pin "18") (pinfunction "OUT1_18") (pintype "open_collector"))
    )
    (net (code "99") (name "OUTA2") (class "Default")
      (node (ref "JP3") (pin "4") (pinfunction "4_4") (pintype "passive"))
      (node (ref "U_OCA") (pin "17") (pinfunction "OUT2_17") (pintype "open_collector"))
    )
    (net (code "100") (name "OUTA3") (class "Default")
      (node (ref "JP3") (pin "6") (pinfunction "6_6") (pintype "passive"))
      (node (ref "U_OCA") (pin "16") (pinfunction "OUT3_16") (pintype "open_collector"))
    )
    (net (code "101") (name "OUTA4") (class "Default")
      (node (ref "JP3") (pin "8") (pinfunction "8_8") (pintype "passive"))
      (node (ref "U_OCA") (pin "15") (pinfunction "OUT4_15") (pintype "open_collector"))
    )
    (net (code "102") (name "OUTA5") (class "Default")
      (node (ref "JP3") (pin "10") (pinfunction "10_10") (pintype "passive"))
      (node (ref "U_OCA") (pin "14") (pinfunction "OUT5_14") (pintype "open_collector"))
    )
    (net (code "103") (name "OUTA6") (class "Default")
      (node (ref "JP3") (pin "12") (pinfunction "12_12") (pintype "passive"))
      (node (ref "U_OCA") (pin "13") (pinfunction "OUT6_13") (pintype "open_collector"))
    )
    (net (code "104") (name "OUTA7") (class "Default")
      (node (ref "JP3") (pin "14") (pinfunction "14_14") (pintype "passive"))
      (node (ref "U_OCA") (pin "12") (pinfunction "OUT7_12") (pintype "open_collector"))
    )
    (net (code "105") (name "OUTA8") (class "Default")
      (node (ref "JP3") (pin "16") (pinfunction "16_16") (pintype "passive"))
      (node (ref "U_OCA") (pin "11") (pinfunction "OUT8_11") (pintype "open_collector"))
    )
    (net (code "106") (name "OUTB1") (class "Default")
      (node (ref "JP3") (pin "18") (pinfunction "18_18") (pintype "passive"))
      (node (ref "U_OCA1") (pin "18") (pinfunction "OUT1_18") (pintype "open_collector"))
    )
    (net (code "107") (name "OUTB2") (class "Default")
      (node (ref "JP3") (pin "20") (pinfunction "20_20") (pintype "passive"))
      (node (ref "U_OCA1") (pin "17") (pinfunction "OUT2_17") (pintype "open_collector"))
    )
    (net (code "108") (name "OUTB3") (class "Default")
      (node (ref "JP4") (pin "2") (pinfunction "2_2") (pintype "passive"))
      (node (ref "U_OCA1") (pin "16") (pinfunction "OUT3_16") (pintype "open_collector"))
    )
    (net (code "109") (name "OUTB4") (class "Default")
      (node (ref "JP4") (pin "4") (pinfunction "4_4") (pintype "passive"))
      (node (ref "U_OCA1") (pin "15") (pinfunction "OUT4_15") (pintype "open_collector"))
    )
    (net (code "110") (name "OUTB5") (class "Default")
      (node (ref "JP4") (pin "6") (pinfunction "6_6") (pintype "passive"))
      (node (ref "U_OCA1") (pin "14") (pinfunction "OUT5_14") (pintype "open_collector"))
    )
    (net (code "111") (name "OUTB6") (class "Default")
      (node (ref "JP4") (pin "8") (pinfunction "8_8") (pintype "passive"))
      (node (ref "U_OCA1") (pin "13") (pinfunction "OUT6_13") (pintype "open_collector"))
    )
    (net (code "112") (name "OUTB7") (class "Default")
      (node (ref "JP4") (pin "10") (pinfunction "10_10") (pintype "passive"))
      (node (ref "U_OCA1") (pin "12") (pinfunction "OUT7_12") (pintype "open_collector"))
    )
    (net (code "113") (name "OUTB8") (class "Default")
      (node (ref "JP4") (pin "12") (pinfunction "12_12") (pintype "passive"))
      (node (ref "U_OCA1") (pin "11") (pinfunction "OUT8_11") (pintype "open_collector"))
    )
    (net (code "114") (name "OUTC1") (class "Default")
      (node (ref "JP4") (pin "14") (pinfunction "14_14") (pintype "passive"))
      (node (ref "U_OCA2") (pin "18") (pinfunction "OUT1_18") (pintype "open_collector"))
    )
    (net (code "115") (name "OUTC2") (class "Default")
      (node (ref "JP4") (pin "16") (pinfunction "16_16") (pintype "passive"))
      (node (ref "U_OCA2") (pin "17") (pinfunction "OUT2_17") (pintype "open_collector"))
    )
    (net (code "116") (name "OUTC3") (class "Default")
      (node (ref "JP4") (pin "18") (pinfunction "18_18") (pintype "passive"))
      (node (ref "U_OCA2") (pin "16") (pinfunction "OUT3_16") (pintype "open_collector"))
    )
    (net (code "117") (name "OUTC4") (class "Default")
      (node (ref "JP4") (pin "20") (pinfunction "20_20") (pintype "passive"))
      (node (ref "U_OCA2") (pin "15") (pinfunction "OUT4_15") (pintype "open_collector"))
    )
    (net (code "118") (name "OUTC5") (class "Default")
      (node (ref "JP5") (pin "2") (pinfunction "2_2") (pintype "passive"))
      (node (ref "U_OCA2") (pin "14") (pinfunction "OUT5_14") (pintype "open_collector"))
    )
    (net (code "119") (name "OUTC6") (class "Default")
      (node (ref "JP5") (pin "4") (pinfunction "4_4") (pintype "passive"))
      (node (ref "U_OCA2") (pin "13") (pinfunction "OUT6_13") (pintype "open_collector"))
    )
    (net (code "120") (name "OUTC7") (class "Default")
      (node (ref "JP5") (pin "6") (pinfunction "6_6") (pintype "passive"))
      (node (ref "U_OCA2") (pin "12") (pinfunction "OUT7_12") (pintype "open_collector"))
    )
    (net (code "121") (name "OUTC8") (class "Default")
      (node (ref "JP5") (pin "8") (pinfunction "8_8") (pintype "passive"))
      (node (ref "U_OCA2") (pin "11") (pinfunction "OUT8_11") (pintype "open_collector"))
    )
    (net (code "122") (name "OUTD1") (class "Default")
      (node (ref "JP5") (pin "10") (pinfunction "10_10") (pintype "passive"))
      (node (ref "U_OCA3") (pin "18") (pinfunction "OUT1_18") (pintype "open_collector"))
    )
    (net (code "123") (name "OUTD2") (class "Default")
      (node (ref "JP5") (pin "12") (pinfunction "12_12") (pintype "passive"))
      (node (ref "U_OCA3") (pin "17") (pinfunction "OUT2_17") (pintype "open_collector"))
    )
    (net (code "124") (name "OUTD3") (class "Default")
      (node (ref "JP5") (pin "14") (pinfunction "14_14") (pintype "passive"))
      (node (ref "U_OCA3") (pin "16") (pinfunction "OUT3_16") (pintype "open_collector"))
    )
    (net (code "125") (name "OUTD4") (class "Default")
      (node (ref "JP5") (pin "16") (pinfunction "16_16") (pintype "passive"))
      (node (ref "U_OCA3") (pin "15") (pinfunction "OUT4_15") (pintype "open_collector"))
    )
    (net (code "126") (name "OUTD5") (class "Default")
      (node (ref "JP5") (pin "18") (pinfunction "18_18") (pintype "passive"))
      (node (ref "U_OCA3") (pin "14") (pinfunction "OUT5_14") (pintype "open_collector"))
    )
    (net (code "127") (name "OUTD6") (class "Default")
      (node (ref "JP5") (pin "20") (pinfunction "20_20") (pintype "passive"))
      (node (ref "U_OCA3") (pin "13") (pinfunction "OUT6_13") (pintype "open_collector"))
    )
    (net (code "128") (name "OUTD7") (class "Default")
      (node (ref "JP6") (pin "2") (pinfunction "2_2") (pintype "passive"))
      (node (ref "U_OCA3") (pin "12") (pinfunction "OUT7_12") (pintype "open_collector"))
    )
    (net (code "129") (name "OUTD8") (class "Default")
      (node (ref "JP6") (pin "4") (pinfunction "4_4") (pintype "passive"))
      (node (ref "U_OCA3") (pin "11") (pinfunction "OUT8_11") (pintype "open_collector"))
    )
    (net (code "130") (name "OUTE1") (class "Default")
      (node (ref "JP6") (pin "6") (pinfunction "6_6") (pintype "passive"))
      (node (ref "U_OCA4") (pin "18") (pinfunction "OUT1_18") (pintype "open_collector"))
    )
    (net (code "131") (name "OUTE2") (class "Default")
      (node (ref "JP6") (pin "8") (pinfunction "8_8") (pintype "passive"))
      (node (ref "U_OCA4") (pin "17") (pinfunction "OUT2_17") (pintype "open_collector"))
    )
    (net (code "132") (name "OUTE3") (class "Default")
      (node (ref "JP6") (pin "10") (pinfunction "10_10") (pintype "passive"))
      (node (ref "U_OCA4") (pin "16") (pinfunction "OUT3_16") (pintype "open_collector"))
    )
    (net (code "133") (name "OUTE4") (class "Default")
      (node (ref "JP6") (pin "12") (pinfunction "12_12") (pintype "passive"))
      (node (ref "U_OCA4") (pin "15") (pinfunction "OUT4_15") (pintype "open_collector"))
    )
    (net (code "134") (name "OUTE5") (class "Default")
      (node (ref "JP6") (pin "14") (pinfunction "14_14") (pintype "passive"))
      (node (ref "U_OCA4") (pin "14") (pinfunction "OUT5_14") (pintype "open_collector"))
    )
    (net (code "135") (name "OUTE6") (class "Default")
      (node (ref "JP6") (pin "16") (pinfunction "16_16") (pintype "passive"))
      (node (ref "U_OCA4") (pin "13") (pinfunction "OUT6_13") (pintype "open_collector"))
    )
    (net (code "136") (name "OUTE7") (class "Default")
      (node (ref "JP6") (pin "18") (pinfunction "18_18") (pintype "passive"))
      (node (ref "U_OCA4") (pin "12") (pinfunction "OUT7_12") (pintype "open_collector"))
    )
    (net (code "137") (name "OUTE8") (class "Default")
      (node (ref "JP6") (pin "20") (pinfunction "20_20") (pintype "passive"))
      (node (ref "U_OCA4") (pin "11") (pinfunction "OUT8_11") (pintype "open_collector"))
    )
    (net (code "138") (name "PL") (class "Default")
      (node (ref "JP1") (pin "7") (pinfunction "7_7") (pintype "passive"))
      (node (ref "JP2") (pin "7") (pinfunction "7_7") (pintype "passive"))
      (node (ref "SHIFT1") (pin "1") (pinfunction "SH/~{LD}_1") (pintype "input"))
      (node (ref "SHIFT2") (pin "1") (pinfunction "SH/~{LD}_1") (pintype "input"))
      (node (ref "SHIFT3") (pin "1") (pinfunction "SH/~{LD}_1") (pintype "input"))
      (node (ref "SHIFT4") (pin "1") (pinfunction "SH/~{LD}_1") (pintype "input"))
      (node (ref "SHIFT5") (pin "1") (pinfunction "SH/~{LD}_1") (pintype "input"))
    )
    (net (code "139") (name "Q7") (class "Default")
      (node (ref "JP1") (pin "1") (pinfunction "1_1") (pintype "passive"))
      (node (ref "SHIFT1") (pin "9") (pinfunction "QH_9") (pintype "output"))
    )
    (net (code "140") (name "Q7_2") (class "Default")
      (node (ref "JP2") (pin "1") (pinfunction "1_1") (pintype "passive"))
      (node (ref "SHIFT5") (pin "10") (pinfunction "SER_10") (pintype "input"))
    )
    (net (code "141") (name "SHCP") (class "Default")
      (node (ref "JP1") (pin "8") (pinfunction "8_8") (pintype "passive"))
      (node (ref "JP2") (pin "8") (pinfunction "8_8") (pintype "passive"))
      (node (ref "SHIFTOUTA") (pin "11") (pinfunction "SCK_11") (pintype "input"))
      (node (ref "SHIFTOUTB") (pin "11") (pinfunction "SCK_11") (pintype "input"))
      (node (ref "SHIFTOUTC") (pin "11") (pinfunction "SCK_11") (pintype "input"))
      (node (ref "SHIFTOUTD") (pin "11") (pinfunction "SCK_11") (pintype "input"))
      (node (ref "SHIFTOUTE") (pin "11") (pinfunction "SCK_11") (pintype "input"))
    )
    (net (code "142") (name "SR_DS") (class "Default")
      (node (ref "JP1") (pin "4") (pinfunction "4_4") (pintype "passive"))
      (node (ref "SHIFTOUTA") (pin "14") (pinfunction "SER_14") (pintype "input"))
    )
    (net (code "143") (name "SR_DS_2") (class "Default")
      (node (ref "JP2") (pin "4") (pinfunction "4_4") (pintype "passive"))
      (node (ref "SHIFTOUTE") (pin "9") (pinfunction "QH*_9") (pintype "tri_state"))
    )
    (net (code "144") (name "STCP") (class "Default")
      (node (ref "JP1") (pin "6") (pinfunction "6_6") (pintype "passive"))
      (node (ref "JP2") (pin "6") (pinfunction "6_6") (pintype "passive"))
      (node (ref "SHIFTOUTA") (pin "12") (pinfunction "RCK_12") (pintype "input"))
      (node (ref "SHIFTOUTB") (pin "12") (pinfunction "RCK_12") (pintype "input"))
      (node (ref "SHIFTOUTC") (pin "12") (pinfunction "RCK_12") (pintype "input"))
      (node (ref "SHIFTOUTD") (pin "12") (pinfunction "RCK_12") (pintype "input"))
      (node (ref "SHIFTOUTE") (pin "12") (pinfunction "RCK_12") (pintype "input"))
    )
    (net (code "145") (name "VCC") (class "Default")
      (node (ref "5V") (pin "A") (pinfunction "A_A") (pintype "passive"))
      (node (ref "C10") (pin "2") (pinfunction "2_2") (pintype "passive"))
      (node (ref "C11") (pin "2") (pinfunction "2_2") (pintype "passive"))
      (node (ref "C12") (pin "2") (pinfunction "2_2") (pintype "passive"))
      (node (ref "C2") (pin "2") (pinfunction "2_2") (pintype "passive"))
      (node (ref "C4") (pin "2") (pinfunction "2_2") (pintype "passive"))
      (node (ref "C5") (pin "2") (pinfunction "2_2") (pintype "passive"))
      (node (ref "C6") (pin "2") (pinfunction "2_2") (pintype "passive"))
      (node (ref "C7") (pin "2") (pinfunction "2_2") (pintype "passive"))
      (node (ref "C8") (pin "2") (pinfunction "2_2") (pintype "passive"))
      (node (ref "C9") (pin "2") (pinfunction "2_2") (pintype "passive"))
      (node (ref "R1") (pin "2") (pinfunction "2_2") (pintype "passive"))
      (node (ref "R2") (pin "2") (pinfunction "2_2") (pintype "passive"))
      (node (ref "R3") (pin "2") (pinfunction "2_2") (pintype "passive"))
      (node (ref "R4") (pin "2") (pinfunction "2_2") (pintype "passive"))
      (node (ref "R5") (pin "2") (pinfunction "2_2") (pintype "passive"))
      (node (ref "R6") (pin "2") (pinfunction "2_2") (pintype "passive"))
      (node (ref "R7") (pin "2") (pinfunction "2_2") (pintype "passive"))
      (node (ref "R8") (pin "2") (pinfunction "2_2") (pintype "passive"))
      (node (ref "RN1") (pin "1") (pinfunction "1_1") (pintype "passive"))
      (node (ref "RN2") (pin "1") (pinfunction "1_1") (pintype "passive"))
      (node (ref "RN4") (pin "1") (pinfunction "1_1") (pintype "passive"))
      (node (ref "RN5") (pin "1") (pinfunction "1_1") (pintype "passive"))
      (node (ref "SHIFT1") (pin "16") (pinfunction "VCC_16") (pintype "power_in"))
      (node (ref "SHIFT2") (pin "16") (pinfunction "VCC_16") (pintype "power_in"))
      (node (ref "SHIFT3") (pin "16") (pinfunction "VCC_16") (pintype "power_in"))
      (node (ref "SHIFT4") (pin "16") (pinfunction "VCC_16") (pintype "power_in"))
      (node (ref "SHIFT5") (pin "16") (pinfunction "VCC_16") (pintype "power_in"))
      (node (ref "SHIFTOUTA") (pin "16") (pinfunction "VCC_16") (pintype "power_in"))
      (node (ref "SHIFTOUTB") (pin "16") (pinfunction "VCC_16") (pintype "power_in"))
      (node (ref "SHIFTOUTC") (pin "16") (pinfunction "VCC_16") (pintype "power_in"))
      (node (ref "SHIFTOUTD") (pin "16") (pinfunction "VCC_16") (pintype "power_in"))
      (node (ref "SHIFTOUTE") (pin "16") (pinfunction "VCC_16") (pintype "power_in"))
      (node (ref "U$2") (pin "PAD2") (pinfunction "PAD2_PAD2") (pintype "bidirectional"))
    )
    (net (code "146") (name "unconnected-(SHIFT1A-~{QH}-Pad7)") (class "Default")
      (node (ref "SHIFT1") (pin "7") (pinfunction "~{QH}_7") (pintype "output"))
    )
    (net (code "147") (name "unconnected-(SHIFT2A-~{QH}-Pad7)") (class "Default")
      (node (ref "SHIFT2") (pin "7") (pinfunction "~{QH}_7") (pintype "output"))
    )
    (net (code "148") (name "unconnected-(SHIFT3A-~{QH}-Pad7)") (class "Default")
      (node (ref "SHIFT3") (pin "7") (pinfunction "~{QH}_7") (pintype "output"))
    )
    (net (code "149") (name "unconnected-(SHIFT4A-~{QH}-Pad7)") (class "Default")
      (node (ref "SHIFT4") (pin "7") (pinfunction "~{QH}_7") (pintype "output"))
    )
    (net (code "150") (name "unconnected-(SHIFT5A-~{QH}-Pad7)") (class "Default")
      (node (ref "SHIFT5") (pin "7") (pinfunction "~{QH}_7") (pintype "output"))
    )
  )
)
